# ESP8266Shield.net
KiCad netlist of a schematic drawn in EAGLE
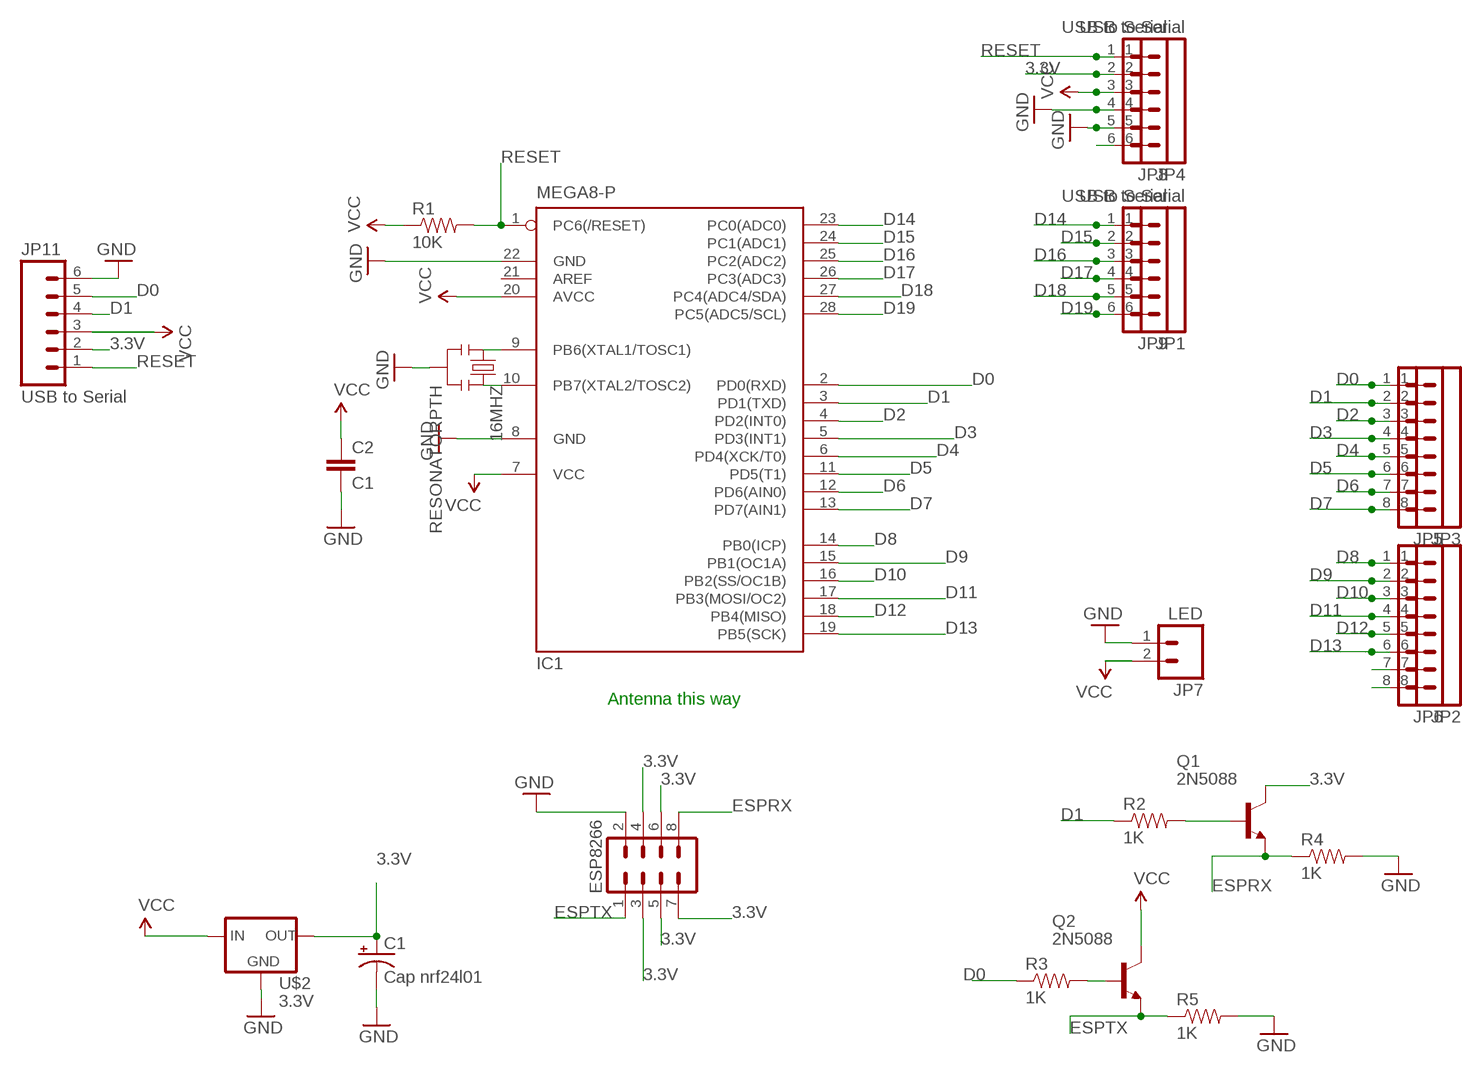
[diagram p0: schematic, sheet 1]

(export (version "E")
  (design (tool "Eeschema 10.0.6"))
  (components
    (comp (ref "16MHZ")
      (value "RESONATORPTH")
      (footprint "eagle-import:RESONATOR-PTH")
      (libsource (lib "eagle-import") (part "RESONATORPTH"))
    )
    (comp (ref "C1")
      (value "Cap nrf24l01")
      (footprint "eagle-import:CPOL-RADIAL-10UF-25V")
      (libsource (lib "eagle-import") (part "CAP_POLPTH2"))
    )
    (comp (ref "C2")
      (value "C1")
      (footprint "eagle-import:CAP-PTH-SMALL")
      (libsource (lib "eagle-import") (part "CAPPTH"))
    )
    (comp (ref "ESP8266")
      (value "M04X2")
      (footprint "eagle-import:2X4")
      (libsource (lib "eagle-import") (part "M04X2"))
    )
    (comp (ref "IC1")
      (value "MEGA8-P")
      (footprint "eagle-import:DIL28-3")
      (libsource (lib "eagle-import") (part "MEGA8-P"))
    )
    (comp (ref "JP1")
      (value "USB to Serial")
      (footprint "eagle-import:1X06")
      (libsource (lib "eagle-import") (part "M06SIP"))
    )
    (comp (ref "JP2")
      (value "M08")
      (footprint "eagle-import:1X08")
      (libsource (lib "eagle-import") (part "M08"))
    )
    (comp (ref "JP3")
      (value "M08")
      (footprint "eagle-import:1X08")
      (libsource (lib "eagle-import") (part "M08"))
    )
    (comp (ref "JP4")
      (value "USB to Serial")
      (footprint "eagle-import:1X06")
      (libsource (lib "eagle-import") (part "M06SIP"))
    )
    (comp (ref "JP5")
      (value "M08")
      (footprint "eagle-import:1X08")
      (libsource (lib "eagle-import") (part "M08"))
    )
    (comp (ref "JP6")
      (value "M08")
      (footprint "eagle-import:1X08")
      (libsource (lib "eagle-import") (part "M08"))
    )
    (comp (ref "JP7")
      (value "LED")
      (footprint "eagle-import:1X02")
      (libsource (lib "eagle-import") (part "M02PTH"))
    )
    (comp (ref "JP8")
      (value "USB to Serial")
      (footprint "eagle-import:1X06")
      (libsource (lib "eagle-import") (part "M06SIP"))
    )
    (comp (ref "JP9")
      (value "USB to Serial")
      (footprint "eagle-import:1X06")
      (libsource (lib "eagle-import") (part "M06SIP"))
    )
    (comp (ref "JP11")
      (value "USB to Serial")
      (footprint "eagle-import:1X06")
      (libsource (lib "eagle-import") (part "M06SIP"))
    )
    (comp (ref "Q1")
      (value "2N5088")
      (footprint "eagle-import:TO92")
      (libsource (lib "eagle-import") (part "2N5088"))
    )
    (comp (ref "Q2")
      (value "2N5088")
      (footprint "eagle-import:TO92")
      (libsource (lib "eagle-import") (part "2N5088"))
    )
    (comp (ref "R1")
      (value "10K")
      (footprint "eagle-import:AXIAL-0.3")
      (libsource (lib "eagle-import") (part "RESISTORPTH1"))
    )
    (comp (ref "R2")
      (value "1K")
      (footprint "eagle-import:AXIAL-0.3")
      (libsource (lib "eagle-import") (part "RESISTORPTH1"))
    )
    (comp (ref "R3")
      (value "1K")
      (footprint "eagle-import:AXIAL-0.3")
      (libsource (lib "eagle-import") (part "RESISTORPTH1"))
    )
    (comp (ref "R4")
      (value "1K")
      (footprint "eagle-import:AXIAL-0.3")
      (libsource (lib "eagle-import") (part "RESISTORPTH1"))
    )
    (comp (ref "R5")
      (value "1K")
      (footprint "eagle-import:AXIAL-0.3")
      (libsource (lib "eagle-import") (part "RESISTORPTH1"))
    )
    (comp (ref "U$2")
      (value "3.3V")
      (footprint "eagle-import:78XXL")
      (libsource (lib "eagle-import") (part "V_REG_LD1117VXX"))
    )
  )
  (nets
    (net (code "1") (name "/3.3V") (class "Default")
      (node (ref "C1") (pin "1") (pinfunction "+_1") (pintype "passive"))
      (node (ref "ESP8266") (pin "3") (pinfunction "3_3") (pintype "passive"))
      (node (ref "ESP8266") (pin "4") (pinfunction "4_4") (pintype "passive"))
      (node (ref "ESP8266") (pin "5") (pinfunction "5_5") (pintype "passive"))
      (node (ref "ESP8266") (pin "6") (pinfunction "6_6") (pintype "passive"))
      (node (ref "ESP8266") (pin "7") (pinfunction "7_7") (pintype "passive"))
      (node (ref "JP11") (pin "2") (pinfunction "2_2") (pintype "passive"))
      (node (ref "JP4") (pin "2") (pinfunction "2_2") (pintype "passive"))
      (node (ref "JP8") (pin "2") (pinfunction "2_2") (pintype "passive"))
      (node (ref "Q1") (pin "1") (pinfunction "C_1") (pintype "passive"))
      (node (ref "U$2") (pin "GND") (pinfunction "OUT_GND") (pintype "output"))
    )
    (net (code "2") (name "/D0") (class "Default")
      (node (ref "IC1") (pin "2") (pinfunction "PD0(RXD)_2") (pintype "bidirectional"))
      (node (ref "JP11") (pin "5") (pinfunction "5_5") (pintype "passive"))
      (node (ref "JP3") (pin "1") (pinfunction "1_1") (pintype "passive"))
      (node (ref "JP5") (pin "1") (pinfunction "1_1") (pintype "passive"))
      (node (ref "R3") (pin "P$1") (pinfunction "1_P$1") (pintype "passive"))
    )
    (net (code "3") (name "/D1") (class "Default")
      (node (ref "IC1") (pin "3") (pinfunction "PD1(TXD)_3") (pintype "bidirectional"))
      (node (ref "JP11") (pin "4") (pinfunction "4_4") (pintype "passive"))
      (node (ref "JP3") (pin "2") (pinfunction "2_2") (pintype "passive"))
      (node (ref "JP5") (pin "2") (pinfunction "2_2") (pintype "passive"))
      (node (ref "R2") (pin "P$1") (pinfunction "1_P$1") (pintype "passive"))
    )
    (net (code "4") (name "/D2") (class "Default")
      (node (ref "IC1") (pin "4") (pinfunction "PD2(INT0)_4") (pintype "bidirectional"))
      (node (ref "JP3") (pin "3") (pinfunction "3_3") (pintype "passive"))
      (node (ref "JP5") (pin "3") (pinfunction "3_3") (pintype "passive"))
    )
    (net (code "5") (name "/D3") (class "Default")
      (node (ref "IC1") (pin "5") (pinfunction "PD3(INT1)_5") (pintype "bidirectional"))
      (node (ref "JP3") (pin "4") (pinfunction "4_4") (pintype "passive"))
      (node (ref "JP5") (pin "4") (pinfunction "4_4") (pintype "passive"))
    )
    (net (code "6") (name "/D4") (class "Default")
      (node (ref "IC1") (pin "6") (pinfunction "PD4(XCK/T0)_6") (pintype "bidirectional"))
      (node (ref "JP3") (pin "5") (pinfunction "5_5") (pintype "passive"))
      (node (ref "JP5") (pin "5") (pinfunction "5_5") (pintype "passive"))
    )
    (net (code "7") (name "/D5") (class "Default")
      (node (ref "IC1") (pin "11") (pinfunction "PD5(T1)_11") (pintype "bidirectional"))
      (node (ref "JP3") (pin "6") (pinfunction "6_6") (pintype "passive"))
      (node (ref "JP5") (pin "6") (pinfunction "6_6") (pintype "passive"))
    )
    (net (code "8") (name "/D6") (class "Default")
      (node (ref "IC1") (pin "12") (pinfunction "PD6(AIN0)_12") (pintype "bidirectional"))
      (node (ref "JP3") (pin "7") (pinfunction "7_7") (pintype "passive"))
      (node (ref "JP5") (pin "7") (pinfunction "7_7") (pintype "passive"))
    )
    (net (code "9") (name "/D7") (class "Default")
      (node (ref "IC1") (pin "13") (pinfunction "PD7(AIN1)_13") (pintype "bidirectional"))
      (node (ref "JP3") (pin "8") (pinfunction "8_8") (pintype "passive"))
      (node (ref "JP5") (pin "8") (pinfunction "8_8") (pintype "passive"))
    )
    (net (code "10") (name "/D8") (class "Default")
      (node (ref "IC1") (pin "14") (pinfunction "PB0(ICP)_14") (pintype "bidirectional"))
      (node (ref "JP2") (pin "1") (pinfunction "1_1") (pintype "passive"))
      (node (ref "JP6") (pin "1") (pinfunction "1_1") (pintype "passive"))
    )
    (net (code "11") (name "/D9") (class "Default")
      (node (ref "IC1") (pin "15") (pinfunction "PB1(OC1A)_15") (pintype "bidirectional"))
      (node (ref "JP2") (pin "2") (pinfunction "2_2") (pintype "passive"))
      (node (ref "JP6") (pin "2") (pinfunction "2_2") (pintype "passive"))
    )
    (net (code "12") (name "/D10") (class "Default")
      (node (ref "IC1") (pin "16") (pinfunction "PB2(SS/OC1B)_16") (pintype "bidirectional"))
      (node (ref "JP2") (pin "3") (pinfunction "3_3") (pintype "passive"))
      (node (ref "JP6") (pin "3") (pinfunction "3_3") (pintype "passive"))
    )
    (net (code "13") (name "/D11") (class "Default")
      (node (ref "IC1") (pin "17") (pinfunction "PB3(MOSI/OC2)_17") (pintype "bidirectional"))
      (node (ref "JP2") (pin "4") (pinfunction "4_4") (pintype "passive"))
      (node (ref "JP6") (pin "4") (pinfunction "4_4") (pintype "passive"))
    )
    (net (code "14") (name "/D12") (class "Default")
      (node (ref "IC1") (pin "18") (pinfunction "PB4(MISO)_18") (pintype "bidirectional"))
      (node (ref "JP2") (pin "5") (pinfunction "5_5") (pintype "passive"))
      (node (ref "JP6") (pin "5") (pinfunction "5_5") (pintype "passive"))
    )
    (net (code "15") (name "/D13") (class "Default")
      (node (ref "IC1") (pin "19") (pinfunction "PB5(SCK)_19") (pintype "bidirectional"))
      (node (ref "JP2") (pin "6") (pinfunction "6_6") (pintype "passive"))
      (node (ref "JP6") (pin "6") (pinfunction "6_6") (pintype "passive"))
    )
    (net (code "16") (name "/D14") (class "Default")
      (node (ref "IC1") (pin "23") (pinfunction "PC0(ADC0)_23") (pintype "bidirectional"))
      (node (ref "JP1") (pin "1") (pinfunction "1_1") (pintype "passive"))
      (node (ref "JP9") (pin "1") (pinfunction "1_1") (pintype "passive"))
    )
    (net (code "17") (name "/D15") (class "Default")
      (node (ref "IC1") (pin "24") (pinfunction "PC1(ADC1)_24") (pintype "bidirectional"))
      (node (ref "JP1") (pin "2") (pinfunction "2_2") (pintype "passive"))
      (node (ref "JP9") (pin "2") (pinfunction "2_2") (pintype "passive"))
    )
    (net (code "18") (name "/D16") (class "Default")
      (node (ref "IC1") (pin "25") (pinfunction "PC2(ADC2)_25") (pintype "bidirectional"))
      (node (ref "JP1") (pin "3") (pinfunction "3_3") (pintype "passive"))
      (node (ref "JP9") (pin "3") (pinfunction "3_3") (pintype "passive"))
    )
    (net (code "19") (name "/D17") (class "Default")
      (node (ref "IC1") (pin "26") (pinfunction "PC3(ADC3)_26") (pintype "bidirectional"))
      (node (ref "JP1") (pin "4") (pinfunction "4_4") (pintype "passive"))
      (node (ref "JP9") (pin "4") (pinfunction "4_4") (pintype "passive"))
    )
    (net (code "20") (name "/D18") (class "Default")
      (node (ref "IC1") (pin "27") (pinfunction "PC4(ADC4/SDA)_27") (pintype "bidirectional"))
      (node (ref "JP1") (pin "5") (pinfunction "5_5") (pintype "passive"))
      (node (ref "JP9") (pin "5") (pinfunction "5_5") (pintype "passive"))
    )
    (net (code "21") (name "/D19") (class "Default")
      (node (ref "IC1") (pin "28") (pinfunction "PC5(ADC5/SCL)_28") (pintype "bidirectional"))
      (node (ref "JP1") (pin "6") (pinfunction "6_6") (pintype "passive"))
      (node (ref "JP9") (pin "6") (pinfunction "6_6") (pintype "passive"))
    )
    (net (code "22") (name "/ESPRX") (class "Default")
      (node (ref "ESP8266") (pin "8") (pinfunction "8_8") (pintype "passive"))
      (node (ref "Q1") (pin "3") (pinfunction "E_3") (pintype "passive"))
      (node (ref "R4") (pin "P$1") (pinfunction "1_P$1") (pintype "passive"))
    )
    (net (code "23") (name "/ESPTX") (class "Default")
      (node (ref "ESP8266") (pin "1") (pinfunction "1_1") (pintype "passive"))
      (node (ref "Q2") (pin "3") (pinfunction "E_3") (pintype "passive"))
      (node (ref "R5") (pin "P$1") (pinfunction "1_P$1") (pintype "passive"))
    )
    (net (code "24") (name "/RESET") (class "Default")
      (node (ref "IC1") (pin "1") (pinfunction "PC6(/RESET)_1") (pintype "bidirectional"))
      (node (ref "JP11") (pin "1") (pinfunction "1_1") (pintype "passive"))
      (node (ref "JP4") (pin "1") (pinfunction "1_1") (pintype "passive"))
      (node (ref "JP8") (pin "1") (pinfunction "1_1") (pintype "passive"))
      (node (ref "R1") (pin "P$2") (pinfunction "2_P$2") (pintype "passive"))
    )
    (net (code "25") (name "GND") (class "Default")
      (node (ref "16MHZ") (pin "2") (pinfunction "2_2") (pintype "passive"))
      (node (ref "C1") (pin "2") (pinfunction "-_2") (pintype "passive"))
      (node (ref "C2") (pin "2") (pinfunction "2_2") (pintype "passive"))
      (node (ref "ESP8266") (pin "2") (pinfunction "2_2") (pintype "passive"))
      (node (ref "IC1") (pin "22") (pinfunction "GND_22") (pintype "power_in"))
      (node (ref "IC1") (pin "8") (pinfunction "GND_8") (pintype "power_in"))
      (node (ref "JP11") (pin "6") (pinfunction "6_6") (pintype "passive"))
      (node (ref "JP4") (pin "4") (pinfunction "4_4") (pintype "passive"))
      (node (ref "JP4") (pin "5") (pinfunction "5_5") (pintype "passive"))
      (node (ref "JP7") (pin "1") (pinfunction "1_1") (pintype "passive"))
      (node (ref "JP8") (pin "4") (pinfunction "4_4") (pintype "passive"))
      (node (ref "JP8") (pin "5") (pinfunction "5_5") (pintype "passive"))
      (node (ref "R4") (pin "P$2") (pinfunction "2_P$2") (pintype "passive"))
      (node (ref "R5") (pin "P$2") (pinfunction "2_P$2") (pintype "passive"))
      (node (ref "U$2") (pin "IN") (pinfunction "GND_IN") (pintype "input"))
    )
    (net (code "26") (name "Net-(IC1-PB6(XTAL1{slash}TOSC1))") (class "Default")
      (node (ref "16MHZ") (pin "1") (pinfunction "1_1") (pintype "passive"))
      (node (ref "IC1") (pin "9") (pinfunction "PB6(XTAL1/TOSC1)_9") (pintype "bidirectional"))
    )
    (net (code "27") (name "Net-(IC1-PB7(XTAL2{slash}TOSC2))") (class "Default")
      (node (ref "16MHZ") (pin "3") (pinfunction "3_3") (pintype "passive"))
      (node (ref "IC1") (pin "10") (pinfunction "PB7(XTAL2/TOSC2)_10") (pintype "bidirectional"))
    )
    (net (code "28") (name "Net-(JP2-Pad7)") (class "Default")
      (node (ref "JP2") (pin "7") (pinfunction "7_7") (pintype "passive"))
      (node (ref "JP6") (pin "7") (pinfunction "7_7") (pintype "passive"))
    )
    (net (code "29") (name "Net-(JP2-Pad8)") (class "Default")
      (node (ref "JP2") (pin "8") (pinfunction "8_8") (pintype "passive"))
      (node (ref "JP6") (pin "8") (pinfunction "8_8") (pintype "passive"))
    )
    (net (code "30") (name "Net-(JP4-Pad6)") (class "Default")
      (node (ref "JP4") (pin "6") (pinfunction "6_6") (pintype "passive"))
      (node (ref "JP8") (pin "6") (pinfunction "6_6") (pintype "passive"))
    )
    (net (code "31") (name "Net-(Q1-B)") (class "Default")
      (node (ref "Q1") (pin "2") (pinfunction "B_2") (pintype "passive"))
      (node (ref "R2") (pin "P$2") (pinfunction "2_P$2") (pintype "passive"))
    )
    (net (code "32") (name "Net-(Q2-B)") (class "Default")
      (node (ref "Q2") (pin "2") (pinfunction "B_2") (pintype "passive"))
      (node (ref "R3") (pin "P$2") (pinfunction "2_P$2") (pintype "passive"))
    )
    (net (code "33") (name "VCC") (class "Default")
      (node (ref "C2") (pin "1") (pinfunction "1_1") (pintype "passive"))
      (node (ref "IC1") (pin "20") (pinfunction "AVCC_20") (pintype "power_in"))
      (node (ref "IC1") (pin "7") (pinfunction "VCC_7") (pintype "power_in"))
      (node (ref "JP11") (pin "3") (pinfunction "3_3") (pintype "passive"))
      (node (ref "JP4") (pin "3") (pinfunction "3_3") (pintype "passive"))
      (node (ref "JP7") (pin "2") (pinfunction "2_2") (pintype "passive"))
      (node (ref "JP8") (pin "3") (pinfunction "3_3") (pintype "passive"))
      (node (ref "Q2") (pin "1") (pinfunction "C_1") (pintype "passive"))
      (node (ref "R1") (pin "P$1") (pinfunction "1_P$1") (pintype "passive"))
      (node (ref "U$2") (pin "OUT") (pinfunction "IN_OUT") (pintype "input"))
    )
    (net (code "34") (name "unconnected-(IC1-AREF-Pad21)") (class "Default")
      (node (ref "IC1") (pin "21") (pinfunction "AREF_21") (pintype "passive"))
    )
  )
)
